# RS485_Tranciever.net
KiCad netlist of a schematic drawn in Altium Designer
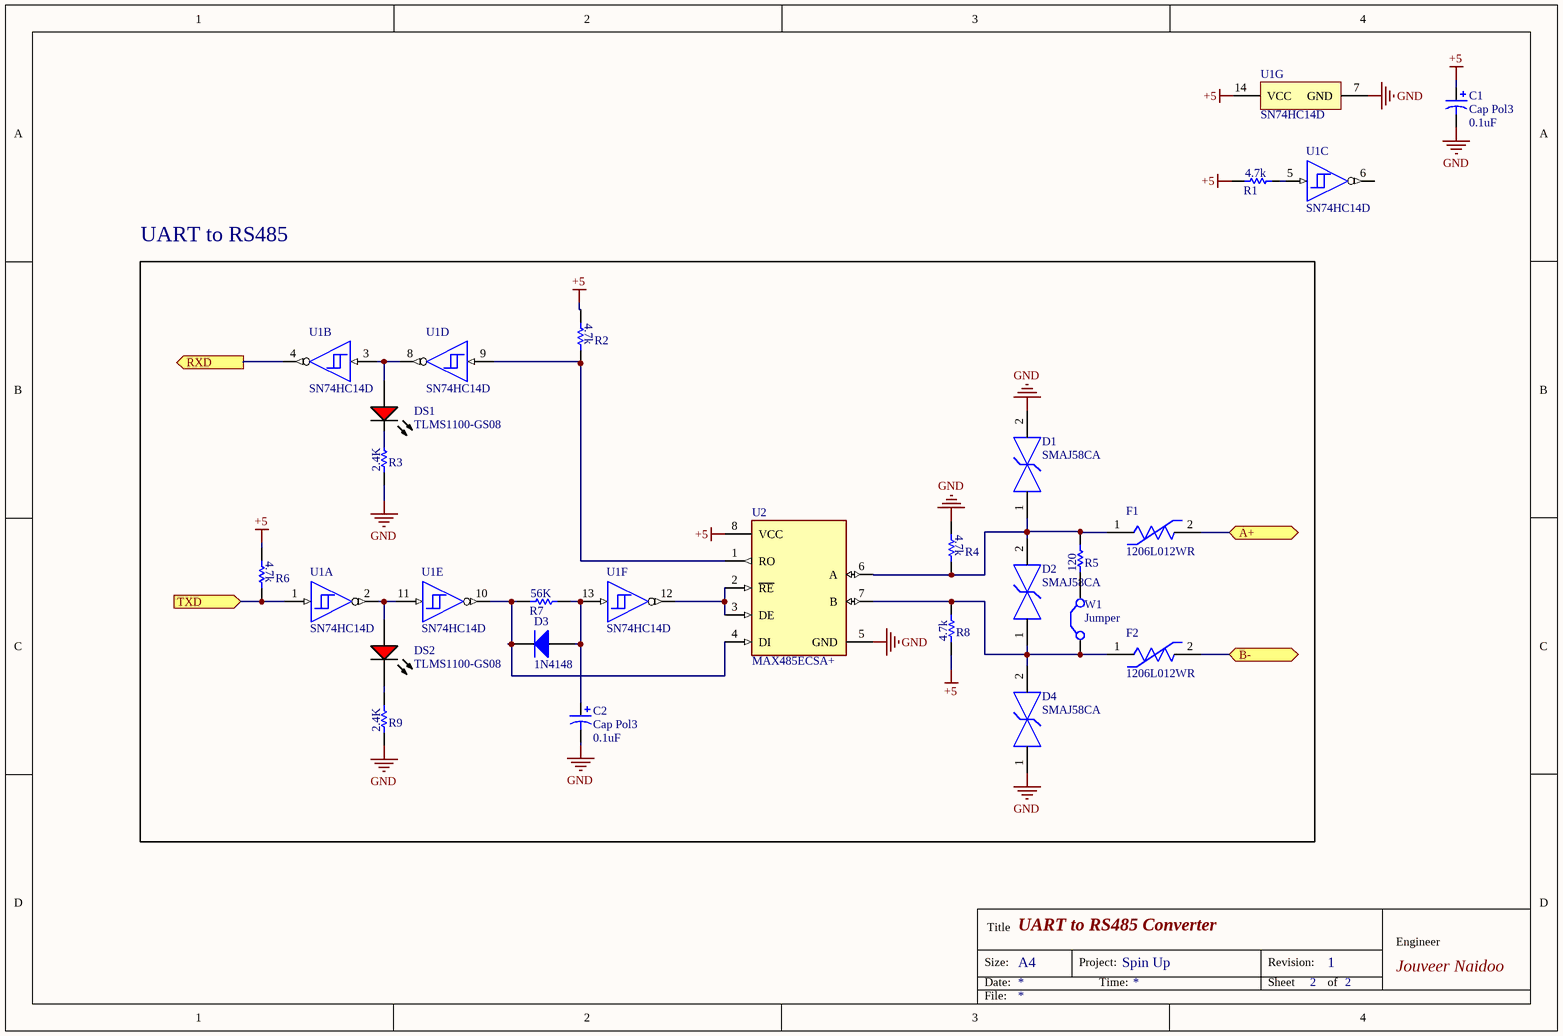
[diagram p0: RS485 Tranciever.SchDoc]

(export (version "E")
  (design (tool "Eeschema 10.0.6"))
  (components
    (comp (ref "C1")
      (value "Cap Pol3")
      (footprint "C0805")
      (description "Polarized Capacitor (Surface Mount)")
      (fields (field (name "ALTIUM_VALUE") "0.1uF") (field (name "PUBLISHER") "Altium Limited"))
      (libsource (lib "Miscellaneous Devices") (part "Cap Pol3"))
    )
    (comp (ref "C2")
      (value "Cap Pol3")
      (footprint "C0805")
      (description "Polarized Capacitor (Surface Mount)")
      (fields (field (name "ALTIUM_VALUE") "0.1uF") (field (name "PUBLISHER") "Altium Limited"))
      (libsource (lib "Miscellaneous Devices") (part "Cap Pol3"))
    )
    (comp (ref "D1")
      (value "SMAJ58CA")
      (footprint "FP-SMAJ-MFG")
      (description "TVS DIODE 58V 93.6V DO214AC")
      (fields
        (field (name "OCTOPART") "https://octopart.com/smaj58ca-littelfuse-350202")
        (field (name "MANUFACTURER") "Littelfuse Inc")
      )
      (libsource (lib "Altium Content Vault") (part "89c663e49c8877d2c9d183c2997548d"))
    )
    (comp (ref "D2")
      (value "SMAJ58CA")
      (footprint "FP-SMAJ-MFG")
      (description "TVS DIODE 58V 93.6V DO214AC")
      (fields
        (field (name "OCTOPART") "https://octopart.com/smaj58ca-littelfuse-350202")
        (field (name "MANUFACTURER") "Littelfuse Inc")
      )
      (libsource (lib "Altium Content Vault") (part "89c663e49c8877d2c9d183c2997548d"))
    )
    (comp (ref "D3")
      (value "1N4148")
      (footprint "NXP-SOD27-2_V")
      (description "High Speed Diode, 100 V, 0.45 A, -65 to 175 degC, 2-Pin SOD27, RoHS, Bulk")
      (fields (field (name "POWER") "500mW") (field (name "MANUFACTURER") "Fairchild"))
      (libsource (lib "Jouveer") (part "D-AK-2"))
    )
    (comp (ref "D4")
      (value "SMAJ58CA")
      (footprint "FP-SMAJ-MFG")
      (description "TVS DIODE 58V 93.6V DO214AC")
      (fields
        (field (name "OCTOPART") "https://octopart.com/smaj58ca-littelfuse-350202")
        (field (name "MANUFACTURER") "Littelfuse Inc")
      )
      (libsource (lib "Altium Content Vault") (part "89c663e49c8877d2c9d183c2997548d"))
    )
    (comp (ref "DS1")
      (value "TLMS1100-GS08")
      (footprint "VISH-TLMX1100_V")
      (description "LED, RED, 2.1 V, -40 to 100 degC, 2-Pin SMD (0603), RoHS, Tape and Reel")
      (fields (field (name "TOLERANCE") "5%"))
      (libsource (lib "Altium Content Vault") (part "LED-RED-AK-2"))
    )
    (comp (ref "DS2")
      (value "TLMS1100-GS08")
      (footprint "VISH-TLMX1100_V")
      (description "LED, RED, 2.1 V, -40 to 100 degC, 2-Pin SMD (0603), RoHS, Tape and Reel")
      (fields (field (name "TOLERANCE") "5%"))
      (libsource (lib "Altium Content Vault") (part "LED-RED-AK-2"))
    )
    (comp (ref "F1")
      (value "1206L012WR")
      (footprint "FP-1206L012WR-MFG")
      (description "PTC RESET FUSE 30V 125MA 1206")
      (libsource (lib "Altium Content Vault") (part "fdf083d5f6389a9a1c4e51137f46658"))
    )
    (comp (ref "F2")
      (value "1206L012WR")
      (footprint "FP-1206L012WR-MFG")
      (description "PTC RESET FUSE 30V 125MA 1206")
      (libsource (lib "Altium Content Vault") (part "fdf083d5f6389a9a1c4e51137f46658"))
    )
    (comp (ref "R1")
      (value "Resistor")
      (footprint "RESC0603X26X15NL03T05")
      (description "Generic SMT Resistor")
      (libsource (lib "Jouveer") (part "RES"))
    )
    (comp (ref "R2")
      (value "Resistor")
      (footprint "RESC0603X26X15NL03T05")
      (description "Generic SMT Resistor")
      (libsource (lib "Jouveer") (part "RES"))
    )
    (comp (ref "R3")
      (value "Resistor")
      (footprint "RESC0603X26X15NL03T05")
      (description "Generic SMT Resistor")
      (libsource (lib "Jouveer") (part "RES"))
    )
    (comp (ref "R4")
      (value "Resistor")
      (footprint "RESC0603X26X15NL03T05")
      (description "Generic SMT Resistor")
      (libsource (lib "Jouveer") (part "RES"))
    )
    (comp (ref "R5")
      (value "Resistor")
      (footprint "RESC0603X26X15NL03T05")
      (description "Generic SMT Resistor")
      (libsource (lib "Jouveer") (part "RES"))
    )
    (comp (ref "R6")
      (value "Resistor")
      (footprint "RESC0603X26X15NL03T05")
      (description "Generic SMT Resistor")
      (libsource (lib "Jouveer") (part "RES"))
    )
    (comp (ref "R7")
      (value "Resistor")
      (footprint "RESC0603X26X15NL03T05")
      (description "Generic SMT Resistor")
      (libsource (lib "Jouveer") (part "RES"))
    )
    (comp (ref "R8")
      (value "Resistor")
      (footprint "RESC0603X26X15NL03T05")
      (description "Generic SMT Resistor")
      (libsource (lib "Jouveer") (part "RES"))
    )
    (comp (ref "R9")
      (value "Resistor")
      (footprint "RESC0603X26X15NL03T05")
      (description "Generic SMT Resistor")
      (libsource (lib "Jouveer") (part "RES"))
    )
    (comp (ref "U1")
      (value "SN74HC14D")
      (footprint "D0014A_N")
      (description "Hex Schmitt-Trigger Inverters, D0014A, TUBE")
      (fields
        (field (name "GENERIC PART NUMBER") "SN74HC14")
        (field (name "MANUFACTURER") "Texas Instruments")
      )
      (libsource (lib "") (part "TI-CD_SNX4XXXXXX4X_19A-14-SCHMITT_1"))
    )
    (comp (ref "U2")
      (value "MAX485ECSA+")
      (footprint "FP-S8-5-MFG")
      (description "IC TXRX RS485/RS422 8-SOIC")
      (fields
        (field (name "OCTOPART") "https://octopart.com/max485ecsa%2B-maxim+integrated-39397871")
        (field (name "MANUFACTURER") "Maxim Integrated")
      )
      (libsource (lib "Altium Content Vault") (part "a5e355d41674bc2bebc6d79e25ee122"))
    )
    (comp (ref "W1")
      (value "Jumper")
      (footprint "RAD-0.2")
      (description "Jumper Wire")
      (fields (field (name "PUBLISHER") "Altium Limited"))
      (libsource (lib "Miscellaneous Devices") (part "Jumper"))
    )
  )
  (nets
    (net (code "1") (name "+5") (class "Default")
      (node (ref "C1") (pin "1") (pinfunction "1_1") (pintype "passive"))
      (node (ref "R1") (pin "1") (pinfunction "1_1") (pintype "passive"))
      (node (ref "R2") (pin "1") (pinfunction "1_1") (pintype "passive"))
      (node (ref "R6") (pin "1") (pinfunction "1_1") (pintype "passive"))
      (node (ref "R8") (pin "1") (pinfunction "1_1") (pintype "passive"))
      (node (ref "U1") (pin "14") (pinfunction "VCC_14") (pintype "power_in"))
      (node (ref "U2") (pin "8") (pinfunction "VCC_8") (pintype "power_in"))
    )
    (net (code "2") (name "/A+") (class "Default")
      (node (ref "F1") (pin "2") (pinfunction "2_2") (pintype "passive"))
    )
    (net (code "3") (name "/B-") (class "Default")
      (node (ref "F2") (pin "2") (pinfunction "2_2") (pintype "passive"))
    )
    (net (code "4") (name "/RXD") (class "Default")
      (node (ref "U1") (pin "4") (pinfunction "~{2Y}_4") (pintype "output"))
    )
    (net (code "5") (name "/TXD") (class "Default")
      (node (ref "R6") (pin "2") (pinfunction "2_2") (pintype "passive"))
      (node (ref "U1") (pin "1") (pinfunction "1A_1") (pintype "input"))
    )
    (net (code "6") (name "GND") (class "Default")
      (node (ref "C1") (pin "2") (pinfunction "2_2") (pintype "passive"))
      (node (ref "C2") (pin "2") (pinfunction "2_2") (pintype "passive"))
      (node (ref "D1") (pin "2") (pinfunction "2_2") (pintype "passive"))
      (node (ref "D4") (pin "1") (pinfunction "1_1") (pintype "passive"))
      (node (ref "R3") (pin "1") (pinfunction "1_1") (pintype "passive"))
      (node (ref "R4") (pin "1") (pinfunction "1_1") (pintype "passive"))
      (node (ref "R9") (pin "1") (pinfunction "1_1") (pintype "passive"))
      (node (ref "U1") (pin "7") (pinfunction "GND_7") (pintype "power_in"))
      (node (ref "U2") (pin "5") (pinfunction "GND_5") (pintype "power_in"))
    )
    (net (code "7") (name "Net-(D3-A)") (class "Default")
      (node (ref "C2") (pin "1") (pinfunction "1_1") (pintype "passive"))
      (node (ref "D3") (pin "1") (pinfunction "A_1") (pintype "passive"))
      (node (ref "R7") (pin "2") (pinfunction "2_2") (pintype "passive"))
      (node (ref "U1") (pin "13") (pinfunction "6A_13") (pintype "input"))
    )
    (net (code "8") (name "Net-(D3-K)") (class "Default")
      (node (ref "D3") (pin "2") (pinfunction "K_2") (pintype "passive"))
      (node (ref "R7") (pin "1") (pinfunction "1_1") (pintype "passive"))
      (node (ref "U1") (pin "10") (pinfunction "~{5Y}_10") (pintype "output"))
      (node (ref "U2") (pin "4") (pinfunction "DI_4") (pintype "input"))
    )
    (net (code "9") (name "Net-(DS1-A)") (class "Default")
      (node (ref "DS1") (pin "1") (pinfunction "A_1") (pintype "passive"))
      (node (ref "U1") (pin "3") (pinfunction "2A_3") (pintype "input"))
      (node (ref "U1") (pin "8") (pinfunction "~{4Y}_8") (pintype "output"))
    )
    (net (code "10") (name "Net-(DS1-K)") (class "Default")
      (node (ref "DS1") (pin "2") (pinfunction "K_2") (pintype "passive"))
      (node (ref "R3") (pin "2") (pinfunction "2_2") (pintype "passive"))
    )
    (net (code "11") (name "Net-(DS2-A)") (class "Default")
      (node (ref "DS2") (pin "1") (pinfunction "A_1") (pintype "passive"))
      (node (ref "U1") (pin "11") (pinfunction "5A_11") (pintype "input"))
      (node (ref "U1") (pin "2") (pinfunction "~{1Y}_2") (pintype "output"))
    )
    (net (code "12") (name "Net-(DS2-K)") (class "Default")
      (node (ref "DS2") (pin "2") (pinfunction "K_2") (pintype "passive"))
      (node (ref "R9") (pin "2") (pinfunction "2_2") (pintype "passive"))
    )
    (net (code "13") (name "Net-(U1C-3A)") (class "Default")
      (node (ref "R1") (pin "2") (pinfunction "2_2") (pintype "passive"))
      (node (ref "U1") (pin "5") (pinfunction "3A_5") (pintype "input"))
    )
    (net (code "14") (name "Net-(U1D-4A)") (class "Default")
      (node (ref "R2") (pin "2") (pinfunction "2_2") (pintype "passive"))
      (node (ref "U1") (pin "9") (pinfunction "4A_9") (pintype "input"))
      (node (ref "U2") (pin "1") (pinfunction "RO_1") (pintype "output"))
    )
    (net (code "15") (name "Net-(U1F-~{6Y})") (class "Default")
      (node (ref "U1") (pin "12") (pinfunction "~{6Y}_12") (pintype "output"))
      (node (ref "U2") (pin "2") (pinfunction "~{RE}_2") (pintype "input"))
      (node (ref "U2") (pin "3") (pinfunction "DE_3") (pintype "input"))
    )
    (net (code "16") (name "Net-(U2-A)") (class "Default")
      (node (ref "D1") (pin "1") (pinfunction "1_1") (pintype "passive"))
      (node (ref "D2") (pin "2") (pinfunction "2_2") (pintype "passive"))
      (node (ref "F1") (pin "1") (pinfunction "1_1") (pintype "passive"))
      (node (ref "R4") (pin "2") (pinfunction "2_2") (pintype "passive"))
      (node (ref "R5") (pin "2") (pinfunction "2_2") (pintype "passive"))
      (node (ref "U2") (pin "6") (pinfunction "A_6") (pintype "bidirectional"))
    )
    (net (code "17") (name "Net-(U2-B)") (class "Default")
      (node (ref "D2") (pin "1") (pinfunction "1_1") (pintype "passive"))
      (node (ref "D4") (pin "2") (pinfunction "2_2") (pintype "passive"))
      (node (ref "F2") (pin "1") (pinfunction "1_1") (pintype "passive"))
      (node (ref "R8") (pin "2") (pinfunction "2_2") (pintype "passive"))
      (node (ref "U2") (pin "7") (pinfunction "B_7") (pintype "bidirectional"))
      (node (ref "W1") (pin "1") (pinfunction "C1_1") (pintype "passive"))
    )
    (net (code "18") (name "Net-(W1-C2)") (class "Default")
      (node (ref "R5") (pin "1") (pinfunction "1_1") (pintype "passive"))
      (node (ref "W1") (pin "2") (pinfunction "C2_2") (pintype "passive"))
    )
    (net (code "19") (name "unconnected-(U1C-~{3Y}-Pad6)") (class "Default")
      (node (ref "U1") (pin "6") (pinfunction "~{3Y}_6") (pintype "output"))
    )
  )
)
